# TraiTimMocKhoa.net
KiCad netlist of a schematic drawn in Altium Designer
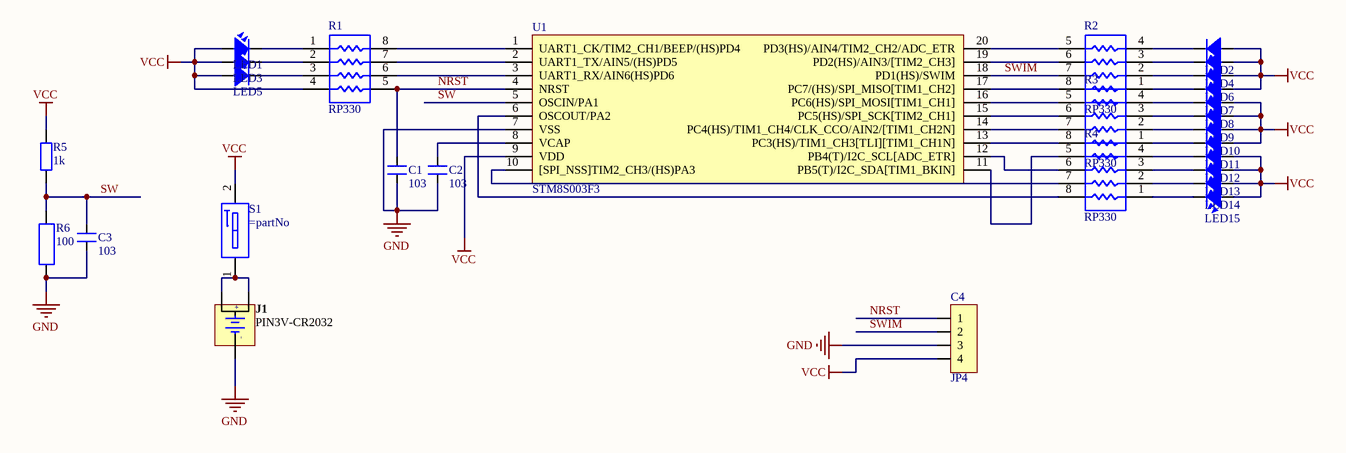
[diagram p0: TraiTimMocKhoa.SchDoc]

(export (version "E")
  (design (tool "Eeschema 10.0.6"))
  (components
    (comp (ref "C1")
      (value "103")
      (footprint "SM-0805")
      (description "Cap SMD")
      (libsource (lib "Tesla_Thinh") (part "CM"))
    )
    (comp (ref "C2")
      (value "103")
      (footprint "SM-0805")
      (description "Cap SMD")
      (libsource (lib "Tesla_Thinh") (part "CM"))
    )
    (comp (ref "C3")
      (value "103")
      (footprint "SM-0805")
      (description "Cap SMD")
      (libsource (lib "Tesla_Thinh") (part "CM"))
    )
    (comp (ref "C4")
      (value "JP4")
      (footprint "JP4-C1T")
      (description "WR-PHD 2.54 mm Angled Socket Header")
      (fields
        (field (name "MANUFACTURER") "Würth Elektronik eiSos GmbH")
        (field (name "PARTNO") "613004143121")
        (field (name "CREATED BY") "Karrer Zheng")
      )
      (libsource (lib "Tesla_Thinh") (part "JP4"))
    )
    (comp (ref "J1")
      (value "PIN3V-CR2032")
      (footprint "PIN3V - CR2032")
      (description "Coin Cell Holder, 21.08 x 15.24 mm SMD")
      (fields
        (field (name "MANUFACTURER") "Memory Protection Devices")
        (field (name "PARTNUMBER") "BK-912-TR")
      )
      (libsource (lib "Tesla_Thinh") (part "PIN3V-CR2032"))
    )
    (comp (ref "LED1")
      (value "LED")
      (footprint "LED-0805-Green")
      (libsource (lib "Tesla_Thinh") (part "LED SMD"))
    )
    (comp (ref "LED2")
      (value "LED")
      (footprint "LED-0805-Green")
      (libsource (lib "Tesla_Thinh") (part "LED SMD"))
    )
    (comp (ref "LED3")
      (value "LED")
      (footprint "LED-0805-Green")
      (libsource (lib "Tesla_Thinh") (part "LED SMD"))
    )
    (comp (ref "LED4")
      (value "LED")
      (footprint "LED-0805-Green")
      (libsource (lib "Tesla_Thinh") (part "LED SMD"))
    )
    (comp (ref "LED5")
      (value "LED")
      (footprint "LED-0805-Green")
      (libsource (lib "Tesla_Thinh") (part "LED SMD"))
    )
    (comp (ref "LED6")
      (value "LED")
      (footprint "LED-0805-Green")
      (libsource (lib "Tesla_Thinh") (part "LED SMD"))
    )
    (comp (ref "LED7")
      (value "LED")
      (footprint "LED-0805-Green")
      (libsource (lib "Tesla_Thinh") (part "LED SMD"))
    )
    (comp (ref "LED8")
      (value "LED")
      (footprint "LED-0805-Green")
      (libsource (lib "Tesla_Thinh") (part "LED SMD"))
    )
    (comp (ref "LED9")
      (value "LED")
      (footprint "LED-0805-Green")
      (libsource (lib "Tesla_Thinh") (part "LED SMD"))
    )
    (comp (ref "LED10")
      (value "LED")
      (footprint "LED-0805-Green")
      (libsource (lib "Tesla_Thinh") (part "LED SMD"))
    )
    (comp (ref "LED11")
      (value "LED")
      (footprint "LED-0805-Green")
      (libsource (lib "Tesla_Thinh") (part "LED SMD"))
    )
    (comp (ref "LED12")
      (value "LED")
      (footprint "LED-0805-Green")
      (libsource (lib "Tesla_Thinh") (part "LED SMD"))
    )
    (comp (ref "LED13")
      (value "LED")
      (footprint "LED-0805-Green")
      (libsource (lib "Tesla_Thinh") (part "LED SMD"))
    )
    (comp (ref "LED14")
      (value "LED")
      (footprint "LED-0805-Green")
      (libsource (lib "Tesla_Thinh") (part "LED SMD"))
    )
    (comp (ref "LED15")
      (value "LED")
      (footprint "LED-0805-Green")
      (libsource (lib "Tesla_Thinh") (part "LED SMD"))
    )
    (comp (ref "R1")
      (value "RP330")
      (footprint "RESCAXS50P160X320X70-8N")
      (libsource (lib "PCB_Project") (part "ResPack"))
    )
    (comp (ref "R2")
      (value "RP330")
      (footprint "RESCAXS50P160X320X70-8N")
      (libsource (lib "PCB_Project") (part "ResPack"))
    )
    (comp (ref "R3")
      (value "RP330")
      (footprint "RESCAXS50P160X320X70-8N")
      (libsource (lib "PCB_Project") (part "ResPack"))
    )
    (comp (ref "R4")
      (value "RP330")
      (footprint "RESCAXS50P160X320X70-8N")
      (libsource (lib "PCB_Project") (part "ResPack"))
    )
    (comp (ref "R5")
      (value "1k")
      (footprint "SM-RES-0805")
      (description "Resistor 1/4W")
      (libsource (lib "Tesla_Thinh") (part "R1/4W"))
    )
    (comp (ref "R6")
      (value "100")
      (footprint "RES-1W")
      (description "Resistor 1W")
      (libsource (lib "Tesla_Thinh") (part "R1W"))
    )
    (comp (ref "S1")
      (value "~")
      (footprint "SW-DIP1-1")
      (description "WS-DITV 2.54 mm small compact THT flat actuator with top tape")
      (fields
        (field (name "MANUFACTURER") "Wurth Elektronik")
        (field (name "PART NO.") "418127160901")
        (field (name "CREATED BY") "Baojun Chen")
      )
      (libsource (lib "Tesla_Thinh") (part "SWDIP1"))
    )
    (comp (ref "U1")
      (value "STM8S003F3")
      (footprint "SSOP20")
      (libsource (lib "Tesla_Thinh") (part "STM8S003F3"))
    )
  )
  (nets
    (net (code "1") (name "/NRST") (class "Default")
      (node (ref "C1") (pin "1") (pinfunction "1_1") (pintype "passive"))
      (node (ref "C4") (pin "1") (pinfunction "1_1") (pintype "passive"))
      (node (ref "R1") (pin "5") (pinfunction "5_5") (pintype "passive"))
      (node (ref "U1") (pin "4") (pinfunction "NRST_4") (pintype "open_collector"))
    )
    (net (code "2") (name "/SW") (class "Default")
      (node (ref "C3") (pin "1") (pinfunction "1_1") (pintype "passive"))
      (node (ref "R5") (pin "2") (pinfunction "2_2") (pintype "passive"))
      (node (ref "R6") (pin "1") (pinfunction "1_1") (pintype "passive"))
      (node (ref "U1") (pin "5") (pinfunction "OSCIN/PA1_5") (pintype "open_collector"))
    )
    (net (code "3") (name "/SWIM") (class "Default")
      (node (ref "C4") (pin "2") (pinfunction "2_2") (pintype "passive"))
      (node (ref "R2") (pin "7") (pinfunction "7_7") (pintype "passive"))
      (node (ref "U1") (pin "18") (pinfunction "PD1(HS)/SWIM_18") (pintype "open_collector"))
    )
    (net (code "4") (name "GND") (class "Default")
      (node (ref "C1") (pin "2") (pinfunction "2_2") (pintype "passive"))
      (node (ref "C2") (pin "2") (pinfunction "2_2") (pintype "passive"))
      (node (ref "C3") (pin "2") (pinfunction "2_2") (pintype "passive"))
      (node (ref "C4") (pin "3") (pinfunction "3_3") (pintype "passive"))
      (node (ref "J1") (pin "3") (pintype "passive"))
      (node (ref "R6") (pin "2") (pinfunction "2_2") (pintype "passive"))
      (node (ref "U1") (pin "7") (pinfunction "VSS_7") (pintype "open_collector"))
    )
    (net (code "5") (name "Net-(J1-Pad1)") (class "Default")
      (node (ref "J1") (pin "1") (pintype "passive"))
      (node (ref "J1") (pin "2") (pintype "passive"))
      (node (ref "S1") (pin "1") (pinfunction "1_1") (pintype "passive"))
    )
    (net (code "6") (name "Net-(LED1-Pad2)") (class "Default")
      (node (ref "LED1") (pin "2") (pinfunction "2_2") (pintype "passive"))
      (node (ref "R1") (pin "1") (pinfunction "1_1") (pintype "passive"))
    )
    (net (code "7") (name "Net-(LED2-Pad2)") (class "Default")
      (node (ref "LED2") (pin "2") (pinfunction "2_2") (pintype "passive"))
      (node (ref "R2") (pin "4") (pinfunction "4_4") (pintype "passive"))
    )
    (net (code "8") (name "Net-(LED3-Pad2)") (class "Default")
      (node (ref "LED3") (pin "2") (pinfunction "2_2") (pintype "passive"))
      (node (ref "R1") (pin "2") (pinfunction "2_2") (pintype "passive"))
    )
    (net (code "9") (name "Net-(LED4-Pad2)") (class "Default")
      (node (ref "LED4") (pin "2") (pinfunction "2_2") (pintype "passive"))
      (node (ref "R2") (pin "3") (pinfunction "3_3") (pintype "passive"))
    )
    (net (code "10") (name "Net-(LED5-Pad2)") (class "Default")
      (node (ref "LED5") (pin "2") (pinfunction "2_2") (pintype "passive"))
      (node (ref "R1") (pin "3") (pinfunction "3_3") (pintype "passive"))
    )
    (net (code "11") (name "Net-(LED6-Pad2)") (class "Default")
      (node (ref "LED6") (pin "2") (pinfunction "2_2") (pintype "passive"))
      (node (ref "R2") (pin "2") (pinfunction "2_2") (pintype "passive"))
    )
    (net (code "12") (name "Net-(LED7-Pad2)") (class "Default")
      (node (ref "LED7") (pin "2") (pinfunction "2_2") (pintype "passive"))
      (node (ref "R2") (pin "1") (pinfunction "1_1") (pintype "passive"))
    )
    (net (code "13") (name "Net-(LED8-Pad2)") (class "Default")
      (node (ref "LED8") (pin "2") (pinfunction "2_2") (pintype "passive"))
      (node (ref "R3") (pin "4") (pinfunction "4_4") (pintype "passive"))
    )
    (net (code "14") (name "Net-(LED9-Pad2)") (class "Default")
      (node (ref "LED9") (pin "2") (pinfunction "2_2") (pintype "passive"))
      (node (ref "R3") (pin "3") (pinfunction "3_3") (pintype "passive"))
    )
    (net (code "15") (name "Net-(LED10-Pad2)") (class "Default")
      (node (ref "LED10") (pin "2") (pinfunction "2_2") (pintype "passive"))
      (node (ref "R3") (pin "2") (pinfunction "2_2") (pintype "passive"))
    )
    (net (code "16") (name "Net-(LED11-Pad2)") (class "Default")
      (node (ref "LED11") (pin "2") (pinfunction "2_2") (pintype "passive"))
      (node (ref "R3") (pin "1") (pinfunction "1_1") (pintype "passive"))
    )
    (net (code "17") (name "Net-(LED12-Pad2)") (class "Default")
      (node (ref "LED12") (pin "2") (pinfunction "2_2") (pintype "passive"))
      (node (ref "R4") (pin "4") (pinfunction "4_4") (pintype "passive"))
    )
    (net (code "18") (name "Net-(LED13-Pad2)") (class "Default")
      (node (ref "LED13") (pin "2") (pinfunction "2_2") (pintype "passive"))
      (node (ref "R4") (pin "3") (pinfunction "3_3") (pintype "passive"))
    )
    (net (code "19") (name "Net-(LED14-Pad2)") (class "Default")
      (node (ref "LED14") (pin "2") (pinfunction "2_2") (pintype "passive"))
      (node (ref "R4") (pin "2") (pinfunction "2_2") (pintype "passive"))
    )
    (net (code "20") (name "Net-(LED15-Pad2)") (class "Default")
      (node (ref "LED15") (pin "2") (pinfunction "2_2") (pintype "passive"))
      (node (ref "R4") (pin "1") (pinfunction "1_1") (pintype "passive"))
    )
    (net (code "21") (name "Net-(U1-OSCOUT{slash}PA2)") (class "Default")
      (node (ref "R4") (pin "8") (pinfunction "8_8") (pintype "passive"))
      (node (ref "U1") (pin "6") (pinfunction "OSCOUT/PA2_6") (pintype "open_collector"))
    )
    (net (code "22") (name "Net-(U1-PB4(T){slash}I2C_SCL[ADC_ETR])") (class "Default")
      (node (ref "R4") (pin "6") (pinfunction "6_6") (pintype "passive"))
      (node (ref "U1") (pin "12") (pinfunction "PB4(T)/I2C_SCL[ADC_ETR]_12") (pintype "open_collector"))
    )
    (net (code "23") (name "Net-(U1-PB5(T){slash}I2C_SDA[TIM1_BKIN])") (class "Default")
      (node (ref "R4") (pin "5") (pinfunction "5_5") (pintype "passive"))
      (node (ref "U1") (pin "11") (pinfunction "PB5(T)/I2C_SDA[TIM1_BKIN]_11") (pintype "open_collector"))
    )
    (net (code "24") (name "Net-(U1-PC3(HS){slash}TIM1_CH3[TLI][TIM1_CH1N])") (class "Default")
      (node (ref "R3") (pin "8") (pinfunction "8_8") (pintype "passive"))
      (node (ref "U1") (pin "13") (pinfunction "PC3(HS)/TIM1_CH3[TLI][TIM1_CH1N]_13") (pintype "open_collector"))
    )
    (net (code "25") (name "Net-(U1-PC4(HS){slash}TIM1_CH4{slash}CLK_CCO{slash}AIN2{slash}[TIM1_CH2N])") (class "Default")
      (node (ref "R3") (pin "7") (pinfunction "7_7") (pintype "passive"))
      (node (ref "U1") (pin "14") (pinfunction "PC4(HS)/TIM1_CH4/CLK_CCO/AIN2/[TIM1_CH2N]_14") (pintype "open_collector"))
    )
    (net (code "26") (name "Net-(U1-PC5(HS){slash}SPI_SCK[TIM2_CH1])") (class "Default")
      (node (ref "R3") (pin "6") (pinfunction "6_6") (pintype "passive"))
      (node (ref "U1") (pin "15") (pinfunction "PC5(HS)/SPI_SCK[TIM2_CH1]_15") (pintype "open_collector"))
    )
    (net (code "27") (name "Net-(U1-PC6(HS){slash}SPI_MOSI[TIM1_CH1])") (class "Default")
      (node (ref "R3") (pin "5") (pinfunction "5_5") (pintype "passive"))
      (node (ref "U1") (pin "16") (pinfunction "PC6(HS)/SPI_MOSI[TIM1_CH1]_16") (pintype "open_collector"))
    )
    (net (code "28") (name "Net-(U1-PC7{slash}(HS){slash}SPI_MISO[TIM1_CH2])") (class "Default")
      (node (ref "R2") (pin "8") (pinfunction "8_8") (pintype "passive"))
      (node (ref "U1") (pin "17") (pinfunction "PC7/(HS)/SPI_MISO[TIM1_CH2]_17") (pintype "open_collector"))
    )
    (net (code "29") (name "Net-(U1-PD2(HS){slash}AIN3{slash}[TIM2_CH3])") (class "Default")
      (node (ref "R2") (pin "6") (pinfunction "6_6") (pintype "passive"))
      (node (ref "U1") (pin "19") (pinfunction "PD2(HS)/AIN3/[TIM2_CH3]_19") (pintype "open_collector"))
    )
    (net (code "30") (name "Net-(U1-PD3(HS){slash}AIN4{slash}TIM2_CH2{slash}ADC_ETR)") (class "Default")
      (node (ref "R2") (pin "5") (pinfunction "5_5") (pintype "passive"))
      (node (ref "U1") (pin "20") (pinfunction "PD3(HS)/AIN4/TIM2_CH2/ADC_ETR_20") (pintype "open_collector"))
    )
    (net (code "31") (name "Net-(U1-UART1_CK{slash}TIM2_CH1{slash}BEEP{slash}(HS)PD4)") (class "Default")
      (node (ref "R1") (pin "8") (pinfunction "8_8") (pintype "passive"))
      (node (ref "U1") (pin "1") (pinfunction "UART1_CK/TIM2_CH1/BEEP/(HS)PD4_1") (pintype "open_collector"))
    )
    (net (code "32") (name "Net-(U1-UART1_RX{slash}AIN6(HS)PD6)") (class "Default")
      (node (ref "R1") (pin "6") (pinfunction "6_6") (pintype "passive"))
      (node (ref "U1") (pin "3") (pinfunction "UART1_RX/AIN6(HS)PD6_3") (pintype "open_collector"))
    )
    (net (code "33") (name "Net-(U1-UART1_TX{slash}AIN5{slash}(HS)PD5)") (class "Default")
      (node (ref "R1") (pin "7") (pinfunction "7_7") (pintype "passive"))
      (node (ref "U1") (pin "2") (pinfunction "UART1_TX/AIN5/(HS)PD5_2") (pintype "open_collector"))
    )
    (net (code "34") (name "Net-(U1-VCAP)") (class "Default")
      (node (ref "C2") (pin "1") (pinfunction "1_1") (pintype "passive"))
      (node (ref "U1") (pin "8") (pinfunction "VCAP_8") (pintype "open_collector"))
    )
    (net (code "35") (name "Net-(U1-[SPI_NSS]TIM2_CH3{slash}(HS)PA3)") (class "Default")
      (node (ref "R4") (pin "7") (pinfunction "7_7") (pintype "passive"))
      (node (ref "U1") (pin "10") (pinfunction "[SPI_NSS]TIM2_CH3/(HS)PA3_10") (pintype "open_collector"))
    )
    (net (code "36") (name "VCC") (class "Default")
      (node (ref "C4") (pin "4") (pinfunction "4_4") (pintype "passive"))
      (node (ref "LED1") (pin "1") (pinfunction "1_1") (pintype "passive"))
      (node (ref "LED10") (pin "1") (pinfunction "1_1") (pintype "passive"))
      (node (ref "LED11") (pin "1") (pinfunction "1_1") (pintype "passive"))
      (node (ref "LED12") (pin "1") (pinfunction "1_1") (pintype "passive"))
      (node (ref "LED13") (pin "1") (pinfunction "1_1") (pintype "passive"))
      (node (ref "LED14") (pin "1") (pinfunction "1_1") (pintype "passive"))
      (node (ref "LED15") (pin "1") (pinfunction "1_1") (pintype "passive"))
      (node (ref "LED2") (pin "1") (pinfunction "1_1") (pintype "passive"))
      (node (ref "LED3") (pin "1") (pinfunction "1_1") (pintype "passive"))
      (node (ref "LED4") (pin "1") (pinfunction "1_1") (pintype "passive"))
      (node (ref "LED5") (pin "1") (pinfunction "1_1") (pintype "passive"))
      (node (ref "LED6") (pin "1") (pinfunction "1_1") (pintype "passive"))
      (node (ref "LED7") (pin "1") (pinfunction "1_1") (pintype "passive"))
      (node (ref "LED8") (pin "1") (pinfunction "1_1") (pintype "passive"))
      (node (ref "LED9") (pin "1") (pinfunction "1_1") (pintype "passive"))
      (node (ref "R1") (pin "4") (pinfunction "4_4") (pintype "passive"))
      (node (ref "R5") (pin "1") (pinfunction "1_1") (pintype "passive"))
      (node (ref "S1") (pin "2") (pinfunction "2_2") (pintype "passive"))
      (node (ref "U1") (pin "9") (pinfunction "VDD_9") (pintype "open_collector"))
    )
  )
)
